# DM1090FFC_IMU.net
KiCad netlist of a schematic drawn in Altium Designer
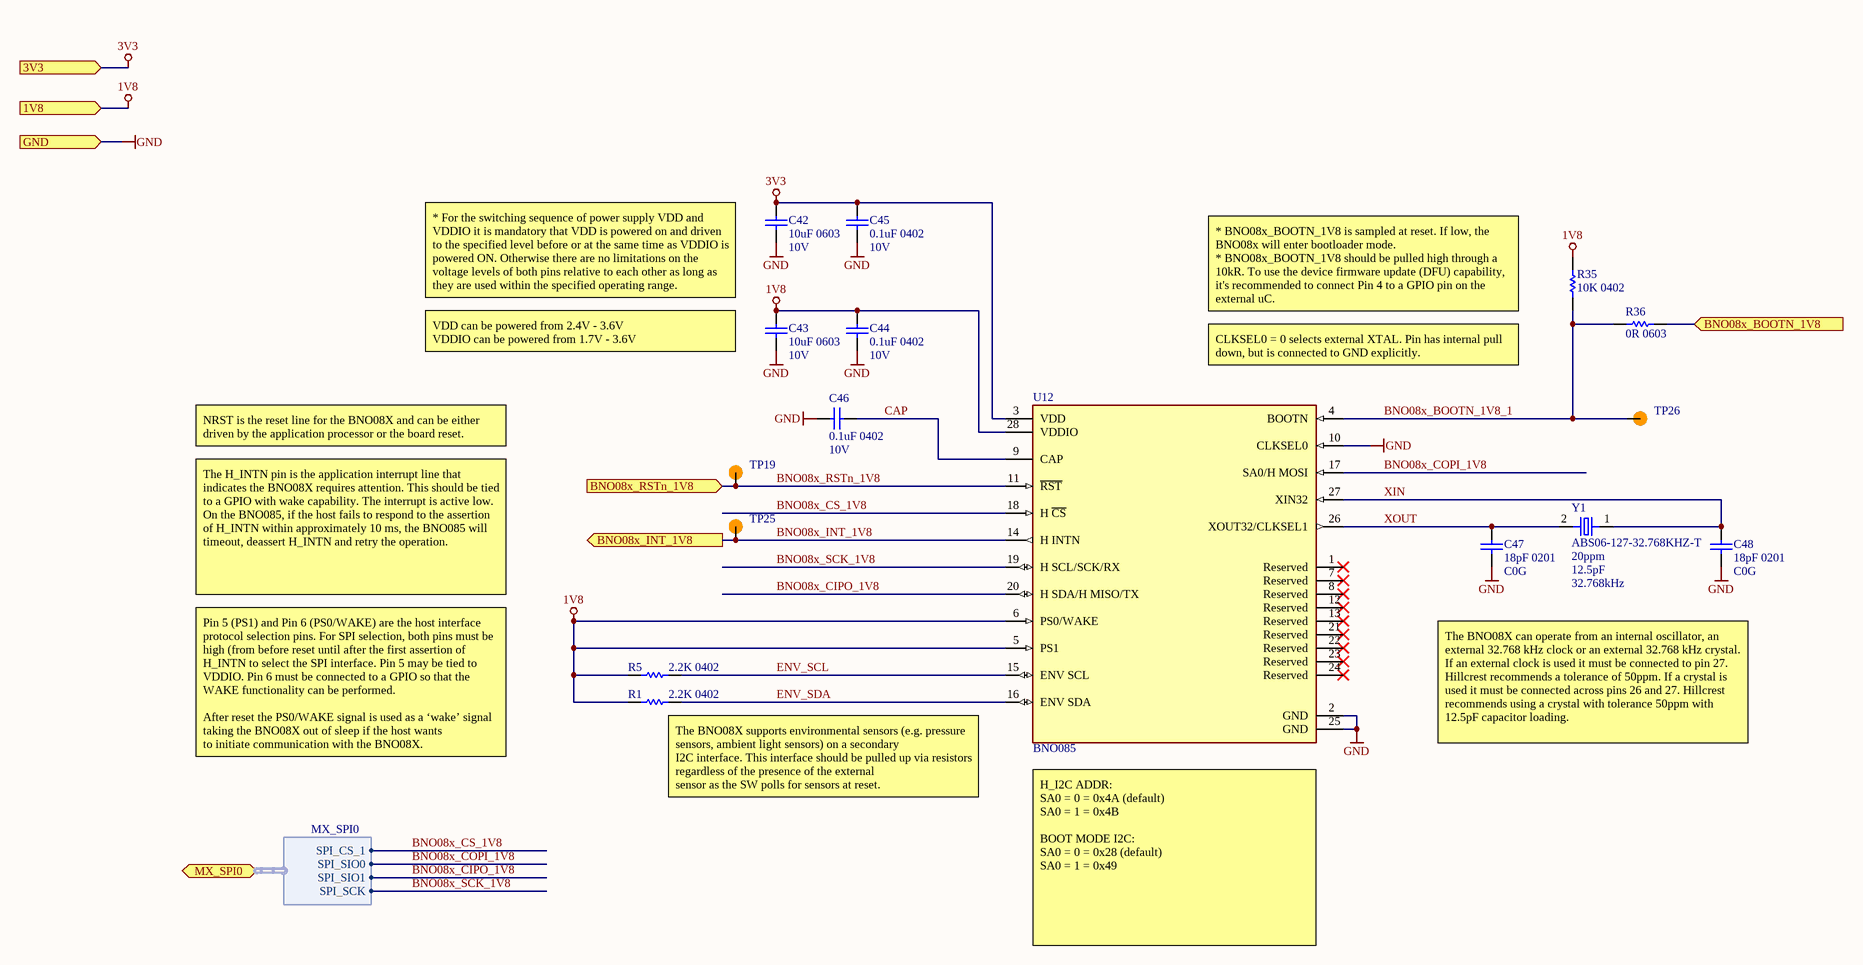
[diagram p0: DM1090FFC_IMU.SchDoc]

(export (version "E")
  (design (tool "Eeschema 10.0.6"))
  (components
    (comp (ref "C42")
      (value "10uF 0603")
      (footprint "CAP_Altium_Vault_Generic:CAPC0603(1608)100_L")
      (description "CAP CER 10UF 10V X5R 0603 20%")
      (fields (field (name "TOLERANCE") "20%") (field (name "VOLTAGE RATING") "10V"))
      (libsource (lib "LuxonisMaster") (part "GRM188R61A106ME69D"))
    )
    (comp (ref "C43")
      (value "10uF 0603")
      (footprint "CAP_Altium_Vault_Generic:CAPC0603(1608)100_L")
      (description "CAP CER 10UF 10V X5R 0603 20%")
      (fields (field (name "TOLERANCE") "20%") (field (name "VOLTAGE RATING") "10V"))
      (libsource (lib "LuxonisMaster") (part "GRM188R61A106ME69D"))
    )
    (comp (ref "C44")
      (value "0.1uF 0402")
      (footprint "CAP_Altium_Vault_Generic:CAPC0402(1005)70_L")
      (description "CAP CER 0.1UF 10V X7R 0402 5%")
      (fields (field (name "TOLERANCE") "5%") (field (name "VOLTAGE RATING") "10V"))
      (libsource (lib "LuxonisMaster") (part "GRM155R71A104JA01D"))
    )
    (comp (ref "C45")
      (value "0.1uF 0402")
      (footprint "CAP_Altium_Vault_Generic:CAPC0402(1005)70_L")
      (description "CAP CER 0.1UF 10V X7R 0402 5%")
      (fields (field (name "TOLERANCE") "5%") (field (name "VOLTAGE RATING") "10V"))
      (libsource (lib "LuxonisMaster") (part "GRM155R71A104JA01D"))
    )
    (comp (ref "C46")
      (value "0.1uF 0402")
      (footprint "CAP_Altium_Vault_Generic:CAPC0402(1005)70_L")
      (description "CAP CER 0.1UF 10V X7R 0402 5%")
      (fields (field (name "TOLERANCE") "5%") (field (name "VOLTAGE RATING") "10V"))
      (libsource (lib "LuxonisMaster") (part "GRM155R71A104JA01D"))
    )
    (comp (ref "C47")
      (value "18pF 0201")
      (footprint "CAP_Altium_Vault_Generic:CAPC0201(0603)33_L")
      (description "Cap Ceramic 18pF 25V C0G 1% Pad SMD 0201 125C T/R")
      (fields (field (name "TOLERANCE") "1%") (field (name "DIELECTRIC") "C0G"))
      (libsource (lib "BW1092_R0M0E0") (part "GRM0335C1E180FA01D"))
    )
    (comp (ref "C48")
      (value "18pF 0201")
      (footprint "CAP_Altium_Vault_Generic:CAPC0201(0603)33_L")
      (description "Cap Ceramic 18pF 25V C0G 1% Pad SMD 0201 125C T/R")
      (fields (field (name "TOLERANCE") "1%") (field (name "DIELECTRIC") "C0G"))
      (libsource (lib "BW1092_R0M0E0") (part "GRM0335C1E180FA01D"))
    )
    (comp (ref "R1")
      (value "2.2K 0402")
      (footprint "RES_Altium_Vault_Generic:RESC0402(1005)_L")
      (description "RES SMD 2.2K OHM 1% 1/16W 0402")
      (fields (field (name "TOLERANCE") "1%"))
      (libsource (lib "LuxonisMaster") (part "RC0402FR-072K2L"))
    )
    (comp (ref "R5")
      (value "2.2K 0402")
      (footprint "RES_Altium_Vault_Generic:RESC0402(1005)_L")
      (description "RES SMD 2.2K OHM 1% 1/16W 0402")
      (fields (field (name "TOLERANCE") "1%"))
      (libsource (lib "LuxonisMaster") (part "RC0402FR-072K2L"))
    )
    (comp (ref "R35")
      (value "10K 0402")
      (footprint "RES_Altium_Vault_Generic:RESC0402(1005)_L")
      (fields (field (name "TOLERANCE") "1%"))
      (libsource (lib "LuxonisMaster") (part "RC0402FR-1310KL"))
    )
    (comp (ref "R36")
      (value "0R 0603")
      (footprint "RES_Altium_Vault_Generic:RESC0603(1608)_L")
      (fields (field (name "TOLERANCE") "5%"))
      (libsource (lib "LuxonisMaster") (part "CRCW06030000Z0EA"))
    )
    (comp (ref "TP19")
      (value "TP100_200_NS")
      (footprint "LuxonisMaster:TP100_200_NS")
      (libsource (lib "LuxonisMaster") (part "TEST_POINT"))
    )
    (comp (ref "TP25")
      (value "TP100_200_NS")
      (footprint "LuxonisMaster:TP100_200_NS")
      (libsource (lib "LuxonisMaster") (part "TEST_POINT"))
    )
    (comp (ref "TP26")
      (value "TP100_200_NS")
      (footprint "LuxonisMaster:TP100_200_NS")
      (libsource (lib "LuxonisMaster") (part "TEST_POINT"))
    )
    (comp (ref "U12")
      (value "BNO085")
      (footprint "BNO085")
      (description "IMU ACCEL/GYRO/MAG I2C 32BIT")
      (libsource (lib "DM1092_R0M0E0") (part "BNO085"))
    )
    (comp (ref "Y1")
      (value "ABS06-127-32.768KHZ-T")
      (footprint "ABS06-127-32.768KHZ-T")
      (description "CRYSTAL 32.768kHz ±20ppm Crystal 12.5pF 90 kOhms 2-SMD, No Lead")
      (fields
        (field (name "FREQUENCY TOLERANCE") "20ppm")
        (field (name "LOAD CAPACITANCE") "12.5pF")
        (field (name "FREQUENCY") "32.768kHz")
      )
      (libsource (lib "DM1092_R0M0E0") (part "ABS06-127-32.768KHZ-T"))
    )
  )
  (nets
    (net (code "2") (name "/BNO08x_BOOTN_1V8") (class "Default")
      (node (ref "R36") (pin "2") (pinfunction "2_2") (pintype "passive"))
    )
    (net (code "3") (name "/BNO08x_BOOTN_1V8_1") (class "Default")
      (node (ref "R35") (pin "1") (pinfunction "1_1") (pintype "passive"))
      (node (ref "R36") (pin "1") (pinfunction "1_1") (pintype "passive"))
      (node (ref "TP26") (pin "1") (pintype "passive"))
      (node (ref "U12") (pin "4") (pinfunction "BOOTN_4") (pintype "input"))
    )
    (net (code "4") (name "/BNO08x_CIPO_1V8") (class "Default")
      (node (ref "U12") (pin "20") (pinfunction "H_SDA/H_MISO/TX_20") (pintype "bidirectional"))
    )
    (net (code "5") (name "/BNO08x_COPI_1V8") (class "Default")
      (node (ref "U12") (pin "17") (pinfunction "SA0/H_MOSI_17") (pintype "input"))
    )
    (net (code "6") (name "/BNO08x_CS_1V8") (class "Default")
      (node (ref "U12") (pin "18") (pinfunction "H_~{CS}_18") (pintype "input"))
    )
    (net (code "7") (name "/BNO08x_INT_1V8") (class "Default")
      (node (ref "TP25") (pin "1") (pintype "passive"))
      (node (ref "U12") (pin "14") (pinfunction "H_INTN_14") (pintype "output"))
    )
    (net (code "8") (name "/BNO08x_RSTn_1V8") (class "Default")
      (node (ref "TP19") (pin "1") (pintype "passive"))
      (node (ref "U12") (pin "11") (pinfunction "~{RST}_11") (pintype "input"))
    )
    (net (code "9") (name "/BNO08x_SCK_1V8") (class "Default")
      (node (ref "U12") (pin "19") (pinfunction "H_SCL/SCK/RX_19") (pintype "bidirectional"))
    )
    (net (code "10") (name "/CAP") (class "Default")
      (node (ref "C46") (pin "1") (pinfunction "1_1") (pintype "passive"))
      (node (ref "U12") (pin "9") (pinfunction "CAP_9") (pintype "passive"))
    )
    (net (code "11") (name "/ENV_SCL") (class "Default")
      (node (ref "R5") (pin "2") (pinfunction "2_2") (pintype "passive"))
      (node (ref "U12") (pin "15") (pinfunction "ENV_SCL_15") (pintype "bidirectional"))
    )
    (net (code "12") (name "/ENV_SDA") (class "Default")
      (node (ref "R1") (pin "2") (pinfunction "2_2") (pintype "passive"))
      (node (ref "U12") (pin "16") (pinfunction "ENV_SDA_16") (pintype "bidirectional"))
    )
    (net (code "13") (name "/XIN") (class "Default")
      (node (ref "C48") (pin "2") (pinfunction "2_2") (pintype "passive"))
      (node (ref "U12") (pin "27") (pinfunction "XIN32_27") (pintype "input"))
      (node (ref "Y1") (pin "1") (pinfunction "1_1") (pintype "passive"))
    )
    (net (code "14") (name "/XOUT") (class "Default")
      (node (ref "C47") (pin "2") (pinfunction "2_2") (pintype "passive"))
      (node (ref "U12") (pin "26") (pinfunction "XOUT32/CLKSEL1_26") (pintype "output"))
      (node (ref "Y1") (pin "2") (pinfunction "2_2") (pintype "passive"))
    )
    (net (code "16") (name "1V8") (class "Default")
      (node (ref "C43") (pin "2") (pinfunction "2_2") (pintype "passive"))
      (node (ref "C44") (pin "2") (pinfunction "2_2") (pintype "passive"))
      (node (ref "R1") (pin "1") (pinfunction "1_1") (pintype "passive"))
      (node (ref "R35") (pin "2") (pinfunction "2_2") (pintype "passive"))
      (node (ref "R5") (pin "1") (pinfunction "1_1") (pintype "passive"))
      (node (ref "U12") (pin "28") (pinfunction "VDDIO_28") (pintype "power_in"))
      (node (ref "U12") (pin "5") (pinfunction "PS1_5") (pintype "input"))
      (node (ref "U12") (pin "6") (pinfunction "PS0/WAKE_6") (pintype "input"))
    )
    (net (code "17") (name "3V3") (class "Default")
      (node (ref "C42") (pin "2") (pinfunction "2_2") (pintype "passive"))
      (node (ref "C45") (pin "2") (pinfunction "2_2") (pintype "passive"))
      (node (ref "U12") (pin "3") (pinfunction "VDD_3") (pintype "power_in"))
    )
    (net (code "18") (name "GND") (class "Default")
      (node (ref "C42") (pin "1") (pinfunction "1_1") (pintype "passive"))
      (node (ref "C43") (pin "1") (pinfunction "1_1") (pintype "passive"))
      (node (ref "C44") (pin "1") (pinfunction "1_1") (pintype "passive"))
      (node (ref "C45") (pin "1") (pinfunction "1_1") (pintype "passive"))
      (node (ref "C46") (pin "2") (pinfunction "2_2") (pintype "passive"))
      (node (ref "C47") (pin "1") (pinfunction "1_1") (pintype "passive"))
      (node (ref "C48") (pin "1") (pinfunction "1_1") (pintype "passive"))
      (node (ref "U12") (pin "10") (pinfunction "CLKSEL0_10") (pintype "input"))
      (node (ref "U12") (pin "2") (pinfunction "GND_2") (pintype "power_in"))
      (node (ref "U12") (pin "25") (pinfunction "GND_25") (pintype "power_in"))
    )
    (net (code "19") (name "unconnected-(U12-Reserved-Pad1)") (class "Default")
      (node (ref "U12") (pin "1") (pinfunction "Reserved_1") (pintype "passive+no_connect"))
    )
    (net (code "20") (name "unconnected-(U12-Reserved-Pad7)") (class "Default")
      (node (ref "U12") (pin "7") (pinfunction "Reserved_7") (pintype "passive+no_connect"))
    )
    (net (code "21") (name "unconnected-(U12-Reserved-Pad8)") (class "Default")
      (node (ref "U12") (pin "8") (pinfunction "Reserved_8") (pintype "passive+no_connect"))
    )
    (net (code "22") (name "unconnected-(U12-Reserved-Pad12)") (class "Default")
      (node (ref "U12") (pin "12") (pinfunction "Reserved_12") (pintype "passive+no_connect"))
    )
    (net (code "23") (name "unconnected-(U12-Reserved-Pad13)") (class "Default")
      (node (ref "U12") (pin "13") (pinfunction "Reserved_13") (pintype "passive+no_connect"))
    )
    (net (code "24") (name "unconnected-(U12-Reserved-Pad21)") (class "Default")
      (node (ref "U12") (pin "21") (pinfunction "Reserved_21") (pintype "passive+no_connect"))
    )
    (net (code "25") (name "unconnected-(U12-Reserved-Pad22)") (class "Default")
      (node (ref "U12") (pin "22") (pinfunction "Reserved_22") (pintype "passive+no_connect"))
    )
    (net (code "26") (name "unconnected-(U12-Reserved-Pad23)") (class "Default")
      (node (ref "U12") (pin "23") (pinfunction "Reserved_23") (pintype "passive+no_connect"))
    )
    (net (code "27") (name "unconnected-(U12-Reserved-Pad24)") (class "Default")
      (node (ref "U12") (pin "24") (pinfunction "Reserved_24") (pintype "passive+no_connect"))
    )
  )
)
